# CHIP4_DUT_Adapter_Board.net
KiCad netlist of a schematic drawn in EAGLE
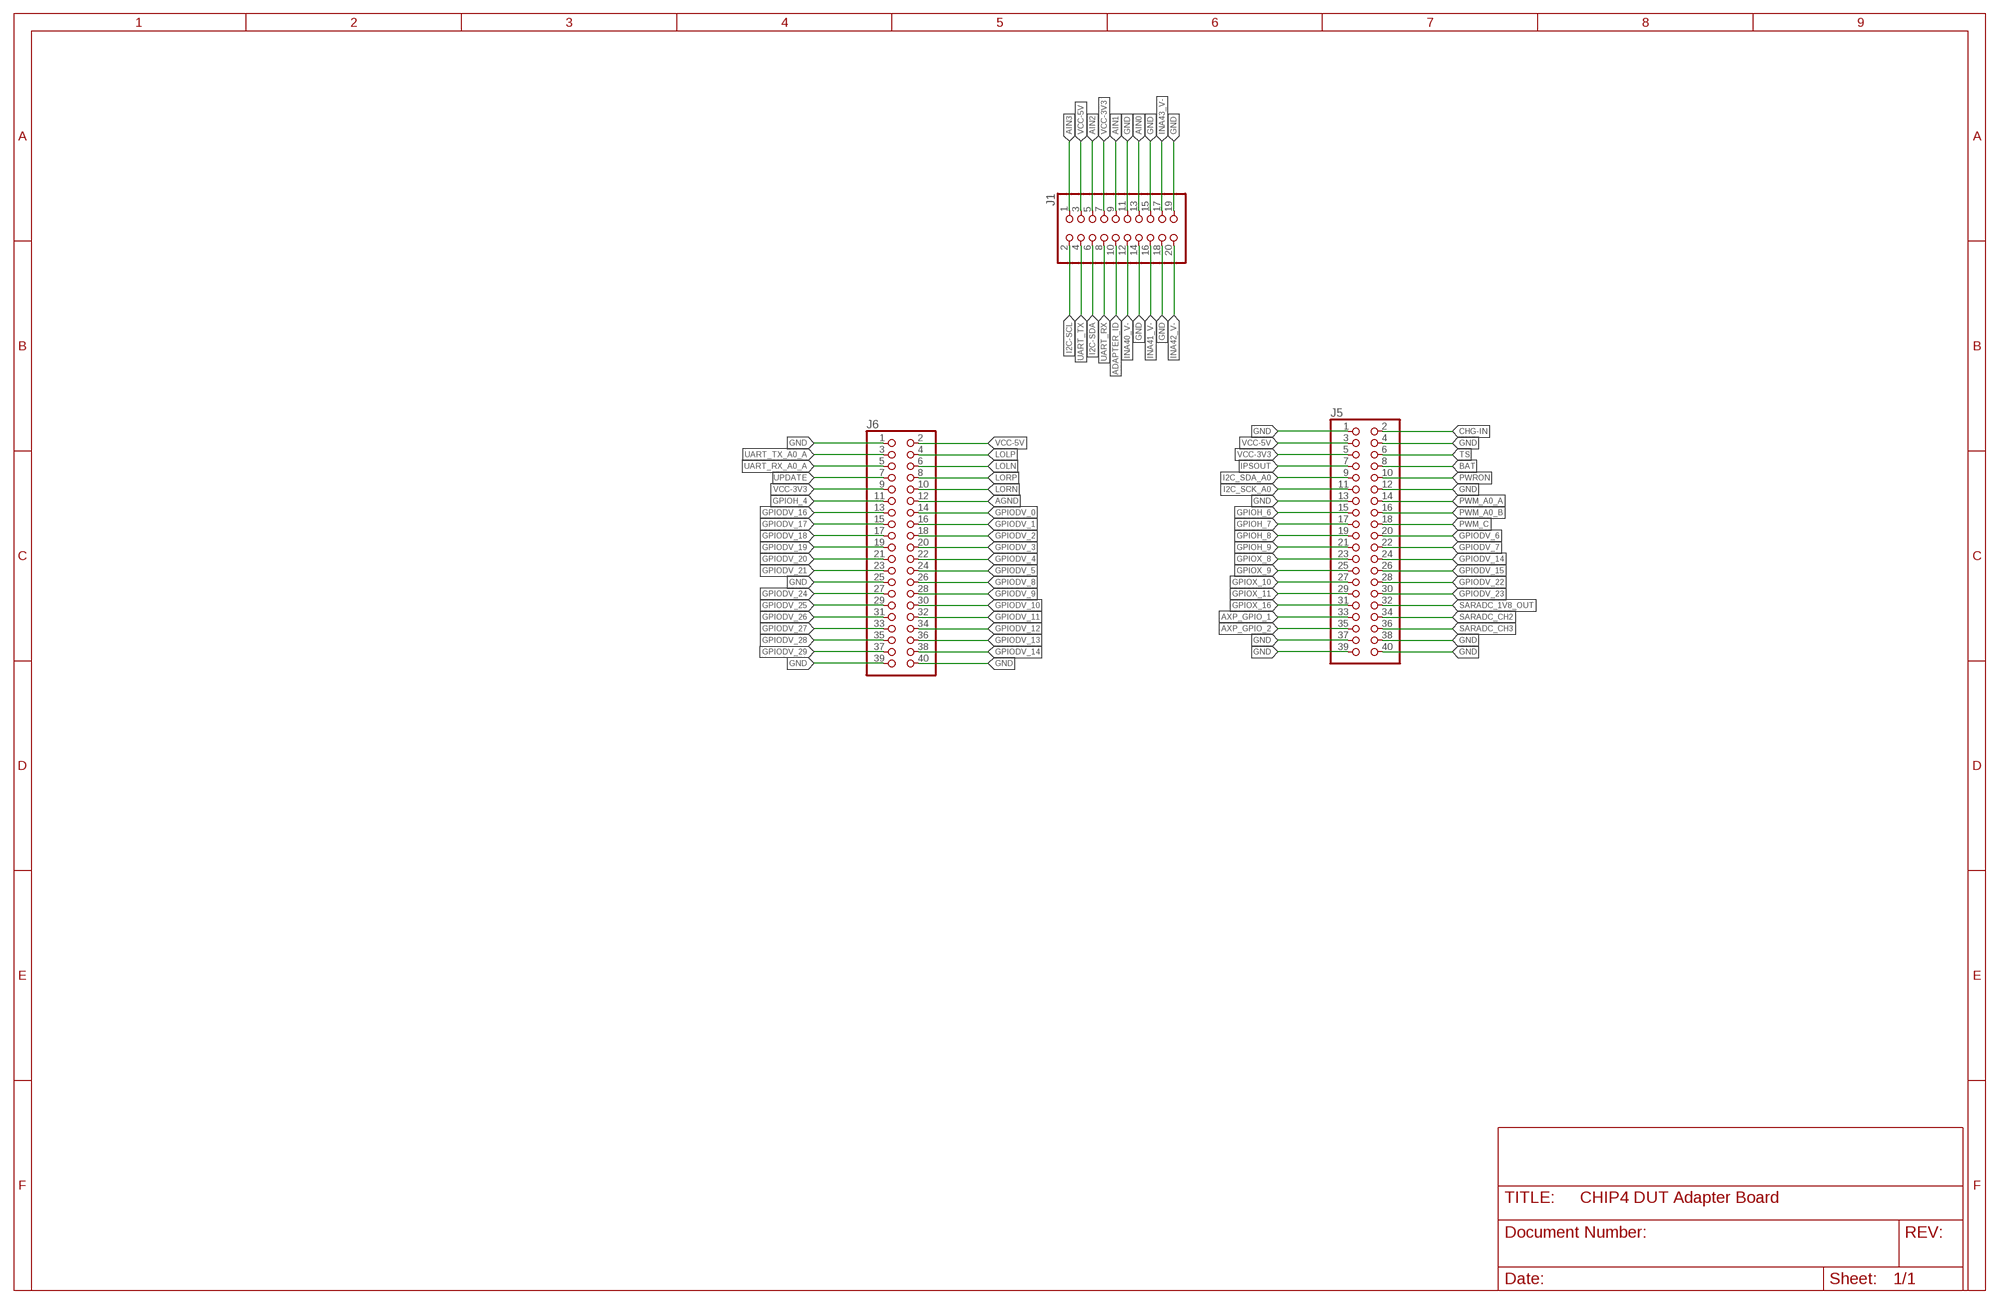
[diagram p0: schematic, sheet 1]

(export (version "E")
  (design (tool "Eeschema 10.0.6"))
  (components
    (comp (ref "J1")
      (value "PINHD-2X10")
      (footprint "eagle-import:2X10")
      (libsource (lib "eagle-import") (part "PINHD-2X10"))
    )
    (comp (ref "J5")
      (value "PINHD-2X20")
      (footprint "eagle-import:2X20")
      (libsource (lib "eagle-import") (part "PINHD-2X20"))
    )
    (comp (ref "J6")
      (value "PINHD-2X20")
      (footprint "eagle-import:2X20")
      (libsource (lib "eagle-import") (part "PINHD-2X20"))
    )
  )
  (nets
    (net (code "1") (name "ADAPTER_ID") (class "Default")
      (node (ref "J1") (pin "10") (pinfunction "10_10") (pintype "passive"))
    )
    (net (code "2") (name "AGND") (class "Default")
      (node (ref "J6") (pin "12") (pinfunction "12_12") (pintype "passive"))
    )
    (net (code "3") (name "AIN0") (class "Default")
      (node (ref "J1") (pin "13") (pinfunction "13_13") (pintype "passive"))
    )
    (net (code "4") (name "AIN1") (class "Default")
      (node (ref "J1") (pin "9") (pinfunction "9_9") (pintype "passive"))
    )
    (net (code "5") (name "AIN2") (class "Default")
      (node (ref "J1") (pin "5") (pinfunction "5_5") (pintype "passive"))
    )
    (net (code "6") (name "AIN3") (class "Default")
      (node (ref "J1") (pin "1") (pinfunction "1_1") (pintype "passive"))
    )
    (net (code "7") (name "AXP_GPIO_1") (class "Default")
      (node (ref "J5") (pin "33") (pinfunction "33_33") (pintype "passive"))
    )
    (net (code "8") (name "AXP_GPIO_2") (class "Default")
      (node (ref "J5") (pin "35") (pinfunction "35_35") (pintype "passive"))
    )
    (net (code "9") (name "BAT") (class "Default")
      (node (ref "J5") (pin "8") (pinfunction "8_8") (pintype "passive"))
    )
    (net (code "10") (name "CHG-IN") (class "Default")
      (node (ref "J5") (pin "2") (pinfunction "2_2") (pintype "passive"))
    )
    (net (code "11") (name "GND") (class "Default")
      (node (ref "J1") (pin "11") (pinfunction "11_11") (pintype "passive"))
      (node (ref "J1") (pin "14") (pinfunction "14_14") (pintype "passive"))
      (node (ref "J1") (pin "15") (pinfunction "15_15") (pintype "passive"))
      (node (ref "J1") (pin "18") (pinfunction "18_18") (pintype "passive"))
      (node (ref "J1") (pin "19") (pinfunction "19_19") (pintype "passive"))
      (node (ref "J5") (pin "1") (pinfunction "1_1") (pintype "passive"))
      (node (ref "J5") (pin "12") (pinfunction "12_12") (pintype "passive"))
      (node (ref "J5") (pin "13") (pinfunction "13_13") (pintype "passive"))
      (node (ref "J5") (pin "37") (pinfunction "37_37") (pintype "passive"))
      (node (ref "J5") (pin "38") (pinfunction "38_38") (pintype "passive"))
      (node (ref "J5") (pin "39") (pinfunction "39_39") (pintype "passive"))
      (node (ref "J5") (pin "4") (pinfunction "4_4") (pintype "passive"))
      (node (ref "J5") (pin "40") (pinfunction "40_40") (pintype "passive"))
      (node (ref "J6") (pin "1") (pinfunction "1_1") (pintype "passive"))
      (node (ref "J6") (pin "25") (pinfunction "25_25") (pintype "passive"))
      (node (ref "J6") (pin "39") (pinfunction "39_39") (pintype "passive"))
      (node (ref "J6") (pin "40") (pinfunction "40_40") (pintype "passive"))
    )
    (net (code "12") (name "GPIODV_0") (class "Default")
      (node (ref "J6") (pin "14") (pinfunction "14_14") (pintype "passive"))
    )
    (net (code "13") (name "GPIODV_1") (class "Default")
      (node (ref "J6") (pin "16") (pinfunction "16_16") (pintype "passive"))
    )
    (net (code "14") (name "GPIODV_2") (class "Default")
      (node (ref "J6") (pin "18") (pinfunction "18_18") (pintype "passive"))
    )
    (net (code "15") (name "GPIODV_3") (class "Default")
      (node (ref "J6") (pin "20") (pinfunction "20_20") (pintype "passive"))
    )
    (net (code "16") (name "GPIODV_4") (class "Default")
      (node (ref "J6") (pin "22") (pinfunction "22_22") (pintype "passive"))
    )
    (net (code "17") (name "GPIODV_5") (class "Default")
      (node (ref "J6") (pin "24") (pinfunction "24_24") (pintype "passive"))
    )
    (net (code "18") (name "GPIODV_6") (class "Default")
      (node (ref "J5") (pin "20") (pinfunction "20_20") (pintype "passive"))
    )
    (net (code "19") (name "GPIODV_7") (class "Default")
      (node (ref "J5") (pin "22") (pinfunction "22_22") (pintype "passive"))
    )
    (net (code "20") (name "GPIODV_8") (class "Default")
      (node (ref "J6") (pin "26") (pinfunction "26_26") (pintype "passive"))
    )
    (net (code "21") (name "GPIODV_9") (class "Default")
      (node (ref "J6") (pin "28") (pinfunction "28_28") (pintype "passive"))
    )
    (net (code "22") (name "GPIODV_10") (class "Default")
      (node (ref "J6") (pin "30") (pinfunction "30_30") (pintype "passive"))
    )
    (net (code "23") (name "GPIODV_11") (class "Default")
      (node (ref "J6") (pin "32") (pinfunction "32_32") (pintype "passive"))
    )
    (net (code "24") (name "GPIODV_12") (class "Default")
      (node (ref "J6") (pin "34") (pinfunction "34_34") (pintype "passive"))
    )
    (net (code "25") (name "GPIODV_13") (class "Default")
      (node (ref "J6") (pin "36") (pinfunction "36_36") (pintype "passive"))
    )
    (net (code "26") (name "GPIODV_14") (class "Default")
      (node (ref "J5") (pin "24") (pinfunction "24_24") (pintype "passive"))
      (node (ref "J6") (pin "38") (pinfunction "38_38") (pintype "passive"))
    )
    (net (code "27") (name "GPIODV_15") (class "Default")
      (node (ref "J5") (pin "26") (pinfunction "26_26") (pintype "passive"))
    )
    (net (code "28") (name "GPIODV_16") (class "Default")
      (node (ref "J6") (pin "13") (pinfunction "13_13") (pintype "passive"))
    )
    (net (code "29") (name "GPIODV_17") (class "Default")
      (node (ref "J6") (pin "15") (pinfunction "15_15") (pintype "passive"))
    )
    (net (code "30") (name "GPIODV_18") (class "Default")
      (node (ref "J6") (pin "17") (pinfunction "17_17") (pintype "passive"))
    )
    (net (code "31") (name "GPIODV_19") (class "Default")
      (node (ref "J6") (pin "19") (pinfunction "19_19") (pintype "passive"))
    )
    (net (code "32") (name "GPIODV_20") (class "Default")
      (node (ref "J6") (pin "21") (pinfunction "21_21") (pintype "passive"))
    )
    (net (code "33") (name "GPIODV_21") (class "Default")
      (node (ref "J6") (pin "23") (pinfunction "23_23") (pintype "passive"))
    )
    (net (code "34") (name "GPIODV_22") (class "Default")
      (node (ref "J5") (pin "28") (pinfunction "28_28") (pintype "passive"))
    )
    (net (code "35") (name "GPIODV_23") (class "Default")
      (node (ref "J5") (pin "30") (pinfunction "30_30") (pintype "passive"))
    )
    (net (code "36") (name "GPIODV_24") (class "Default")
      (node (ref "J6") (pin "27") (pinfunction "27_27") (pintype "passive"))
    )
    (net (code "37") (name "GPIODV_25") (class "Default")
      (node (ref "J6") (pin "29") (pinfunction "29_29") (pintype "passive"))
    )
    (net (code "38") (name "GPIODV_26") (class "Default")
      (node (ref "J6") (pin "31") (pinfunction "31_31") (pintype "passive"))
    )
    (net (code "39") (name "GPIODV_27") (class "Default")
      (node (ref "J6") (pin "33") (pinfunction "33_33") (pintype "passive"))
    )
    (net (code "40") (name "GPIODV_28") (class "Default")
      (node (ref "J6") (pin "35") (pinfunction "35_35") (pintype "passive"))
    )
    (net (code "41") (name "GPIODV_29") (class "Default")
      (node (ref "J6") (pin "37") (pinfunction "37_37") (pintype "passive"))
    )
    (net (code "42") (name "GPIOH_4") (class "Default")
      (node (ref "J6") (pin "11") (pinfunction "11_11") (pintype "passive"))
    )
    (net (code "43") (name "GPIOH_6") (class "Default")
      (node (ref "J5") (pin "15") (pinfunction "15_15") (pintype "passive"))
    )
    (net (code "44") (name "GPIOH_7") (class "Default")
      (node (ref "J5") (pin "17") (pinfunction "17_17") (pintype "passive"))
    )
    (net (code "45") (name "GPIOH_8") (class "Default")
      (node (ref "J5") (pin "19") (pinfunction "19_19") (pintype "passive"))
    )
    (net (code "46") (name "GPIOH_9") (class "Default")
      (node (ref "J5") (pin "21") (pinfunction "21_21") (pintype "passive"))
    )
    (net (code "47") (name "GPIOX_8") (class "Default")
      (node (ref "J5") (pin "23") (pinfunction "23_23") (pintype "passive"))
    )
    (net (code "48") (name "GPIOX_9") (class "Default")
      (node (ref "J5") (pin "25") (pinfunction "25_25") (pintype "passive"))
    )
    (net (code "49") (name "GPIOX_10") (class "Default")
      (node (ref "J5") (pin "27") (pinfunction "27_27") (pintype "passive"))
    )
    (net (code "50") (name "GPIOX_11") (class "Default")
      (node (ref "J5") (pin "29") (pinfunction "29_29") (pintype "passive"))
    )
    (net (code "51") (name "GPIOX_16") (class "Default")
      (node (ref "J5") (pin "31") (pinfunction "31_31") (pintype "passive"))
    )
    (net (code "52") (name "I2C-SCL") (class "Default")
      (node (ref "J1") (pin "2") (pinfunction "2_2") (pintype "passive"))
    )
    (net (code "53") (name "I2C-SDA") (class "Default")
      (node (ref "J1") (pin "6") (pinfunction "6_6") (pintype "passive"))
    )
    (net (code "54") (name "I2C_SCK_A0") (class "Default")
      (node (ref "J5") (pin "11") (pinfunction "11_11") (pintype "passive"))
    )
    (net (code "55") (name "I2C_SDA_A0") (class "Default")
      (node (ref "J5") (pin "9") (pinfunction "9_9") (pintype "passive"))
    )
    (net (code "56") (name "INA40_V-") (class "Default")
      (node (ref "J1") (pin "12") (pinfunction "12_12") (pintype "passive"))
    )
    (net (code "57") (name "INA41_V-") (class "Default")
      (node (ref "J1") (pin "16") (pinfunction "16_16") (pintype "passive"))
    )
    (net (code "58") (name "INA42_V-") (class "Default")
      (node (ref "J1") (pin "20") (pinfunction "20_20") (pintype "passive"))
    )
    (net (code "59") (name "INA43_V-") (class "Default")
      (node (ref "J1") (pin "17") (pinfunction "17_17") (pintype "passive"))
    )
    (net (code "60") (name "IPSOUT") (class "Default")
      (node (ref "J5") (pin "7") (pinfunction "7_7") (pintype "passive"))
    )
    (net (code "61") (name "LOLN") (class "Default")
      (node (ref "J6") (pin "6") (pinfunction "6_6") (pintype "passive"))
    )
    (net (code "62") (name "LOLP") (class "Default")
      (node (ref "J6") (pin "4") (pinfunction "4_4") (pintype "passive"))
    )
    (net (code "63") (name "LORN") (class "Default")
      (node (ref "J6") (pin "10") (pinfunction "10_10") (pintype "passive"))
    )
    (net (code "64") (name "LORP") (class "Default")
      (node (ref "J6") (pin "8") (pinfunction "8_8") (pintype "passive"))
    )
    (net (code "65") (name "PWM_A0_A") (class "Default")
      (node (ref "J5") (pin "14") (pinfunction "14_14") (pintype "passive"))
    )
    (net (code "66") (name "PWM_A0_B") (class "Default")
      (node (ref "J5") (pin "16") (pinfunction "16_16") (pintype "passive"))
    )
    (net (code "67") (name "PWM_C") (class "Default")
      (node (ref "J5") (pin "18") (pinfunction "18_18") (pintype "passive"))
    )
    (net (code "68") (name "PWRON") (class "Default")
      (node (ref "J5") (pin "10") (pinfunction "10_10") (pintype "passive"))
    )
    (net (code "69") (name "SARADC_1V8_OUT") (class "Default")
      (node (ref "J5") (pin "32") (pinfunction "32_32") (pintype "passive"))
    )
    (net (code "70") (name "SARADC_CH2") (class "Default")
      (node (ref "J5") (pin "34") (pinfunction "34_34") (pintype "passive"))
    )
    (net (code "71") (name "SARADC_CH3") (class "Default")
      (node (ref "J5") (pin "36") (pinfunction "36_36") (pintype "passive"))
    )
    (net (code "72") (name "TS") (class "Default")
      (node (ref "J5") (pin "6") (pinfunction "6_6") (pintype "passive"))
    )
    (net (code "73") (name "UART_RX") (class "Default")
      (node (ref "J1") (pin "8") (pinfunction "8_8") (pintype "passive"))
    )
    (net (code "74") (name "UART_RX_A0_A") (class "Default")
      (node (ref "J6") (pin "5") (pinfunction "5_5") (pintype "passive"))
    )
    (net (code "75") (name "UART_TX") (class "Default")
      (node (ref "J1") (pin "4") (pinfunction "4_4") (pintype "passive"))
    )
    (net (code "76") (name "UART_TX_A0_A") (class "Default")
      (node (ref "J6") (pin "3") (pinfunction "3_3") (pintype "passive"))
    )
    (net (code "77") (name "UPDATE") (class "Default")
      (node (ref "J6") (pin "7") (pinfunction "7_7") (pintype "passive"))
    )
    (net (code "78") (name "VCC-3V3") (class "Default")
      (node (ref "J1") (pin "7") (pinfunction "7_7") (pintype "passive"))
      (node (ref "J5") (pin "5") (pinfunction "5_5") (pintype "passive"))
      (node (ref "J6") (pin "9") (pinfunction "9_9") (pintype "passive"))
    )
    (net (code "79") (name "VCC-5V") (class "Default")
      (node (ref "J1") (pin "3") (pinfunction "3_3") (pintype "passive"))
      (node (ref "J5") (pin "3") (pinfunction "3_3") (pintype "passive"))
      (node (ref "J6") (pin "2") (pinfunction "2_2") (pintype "passive"))
    )
  )
)
